# 3_waffling60-MXHS-ANSI_mcu.net
KiCad netlist of a schematic drawn in Altium Designer
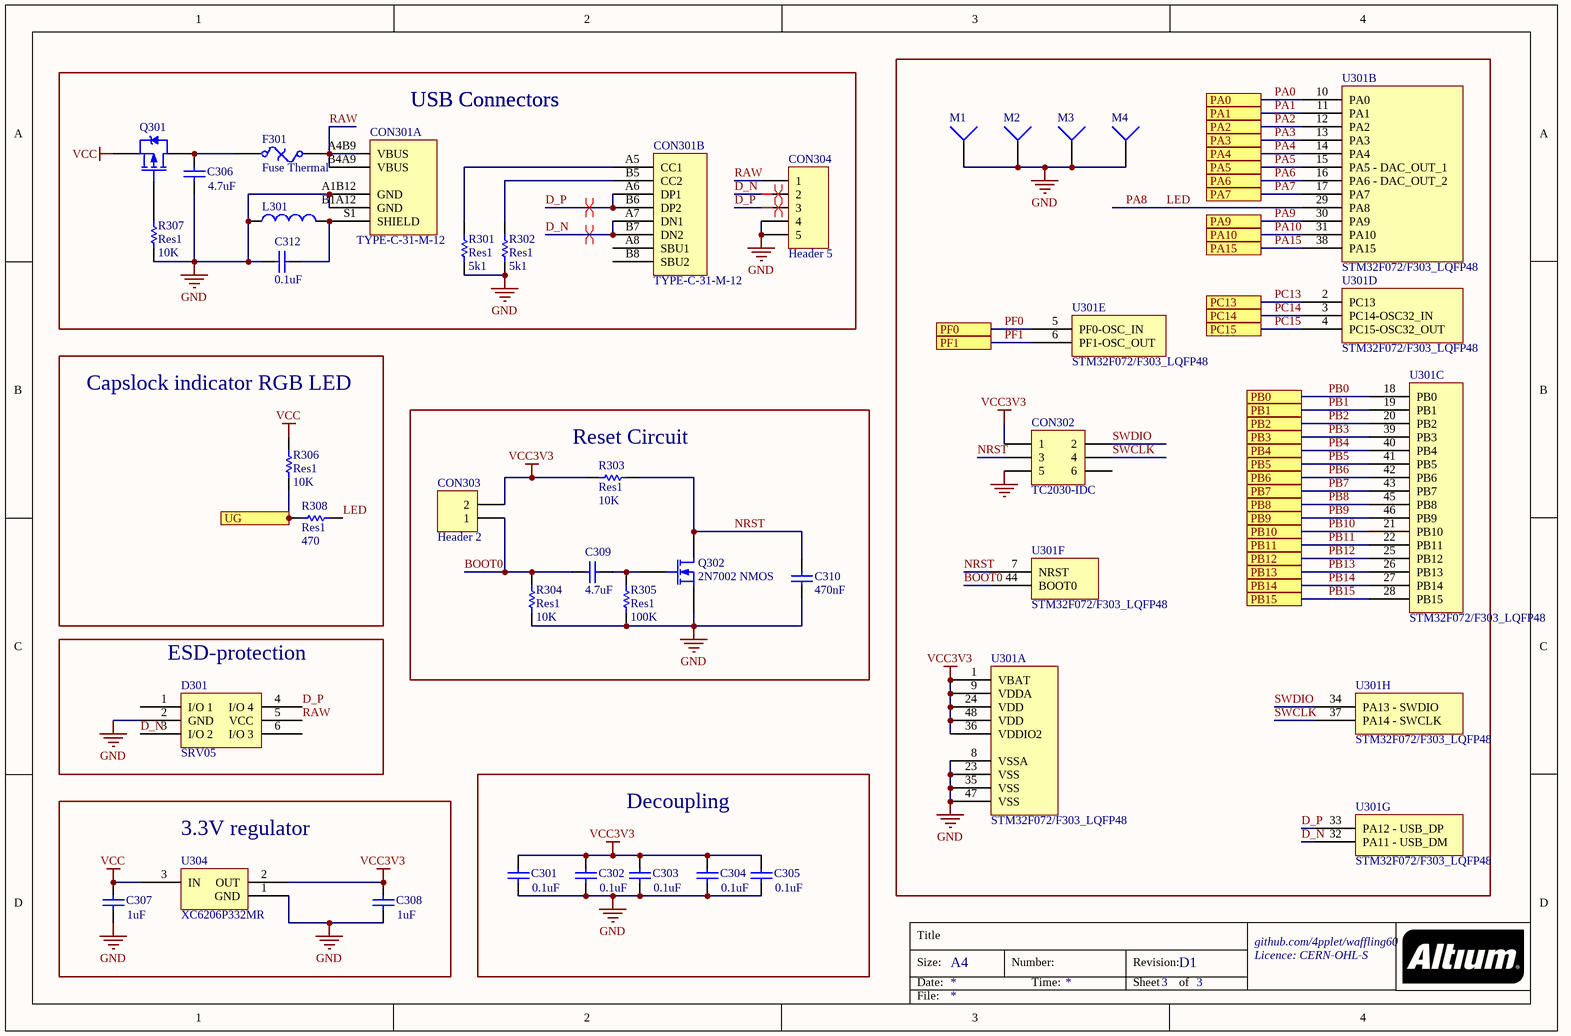
[diagram p0: 3_waffling60-MXHS-ANSI_mcu.SchDoc]

(export (version "E")
  (design (tool "Eeschema 10.0.6"))
  (components
    (comp (ref "C301")
      (value "0.1uF")
      (footprint "C0603[1608]")
      (description "Capacitor")
      (fields (field (name "LCSC PART #") "C14663") (field (name "MRF.PART") "CC0603KRX7R9BB104"))
      (libsource (lib "Miscellaneous Devices") (part "Cap"))
    )
    (comp (ref "C302")
      (value "0.1uF")
      (footprint "C0603[1608]")
      (description "Capacitor")
      (fields (field (name "LCSC PART #") "C14663") (field (name "MRF.PART") "CC0603KRX7R9BB104"))
      (libsource (lib "Miscellaneous Devices") (part "Cap"))
    )
    (comp (ref "C303")
      (value "0.1uF")
      (footprint "C0603[1608]")
      (description "Capacitor")
      (fields (field (name "LCSC PART #") "C14663") (field (name "MRF.PART") "CC0603KRX7R9BB104"))
      (libsource (lib "Miscellaneous Devices") (part "Cap"))
    )
    (comp (ref "C304")
      (value "0.1uF")
      (footprint "C0603[1608]")
      (description "Capacitor")
      (fields (field (name "LCSC PART #") "C14663") (field (name "MRF.PART") "CC0603KRX7R9BB104"))
      (libsource (lib "Miscellaneous Devices") (part "Cap"))
    )
    (comp (ref "C305")
      (value "0.1uF")
      (footprint "C0603[1608]")
      (description "Capacitor")
      (fields (field (name "LCSC PART #") "C14663") (field (name "MRF.PART") "CC0603KRX7R9BB104"))
      (libsource (lib "Miscellaneous Devices") (part "Cap"))
    )
    (comp (ref "C306")
      (value "4.7uF")
      (footprint "C0603[1608]")
      (description "Capacitor")
      (fields (field (name "LCSC PART #") "C19666") (field (name "MRF.PART") "CL10A475KO8NNNC"))
      (libsource (lib "Miscellaneous Devices") (part "Cap"))
    )
    (comp (ref "C307")
      (value "1uF")
      (footprint "C0603[1608]")
      (description "Capacitor")
      (fields (field (name "LCSC PART #") "C15849") (field (name "MRF.PART") "CL10A105KB8NNNC"))
      (libsource (lib "Miscellaneous Devices") (part "Cap"))
    )
    (comp (ref "C308")
      (value "1uF")
      (footprint "C0603[1608]")
      (description "Capacitor")
      (fields (field (name "LCSC PART #") "C15849") (field (name "MRF.PART") "CL10A105KB8NNNC"))
      (libsource (lib "Miscellaneous Devices") (part "Cap"))
    )
    (comp (ref "C309")
      (value "4.7uF")
      (footprint "C0603[1608]")
      (description "Capacitor")
      (fields (field (name "LCSC PART #") "C19666") (field (name "MRF.PART") "CL10A475KO8NNNC"))
      (libsource (lib "Miscellaneous Devices") (part "Cap"))
    )
    (comp (ref "C310")
      (value "470nF")
      (footprint "C0603[1608]")
      (description "Capacitor")
      (fields (field (name "LCSC PART #") "C1623") (field (name "MRF.PART") "CL10B474KA8NNNC"))
      (libsource (lib "Miscellaneous Devices") (part "Cap"))
    )
    (comp (ref "C312")
      (value "0.1uF")
      (footprint "C0603[1608]")
      (description "Capacitor")
      (fields (field (name "LCSC PART #") "C14663") (field (name "MRF.PART") "CC0603KRX7R9BB104"))
      (libsource (lib "Miscellaneous Devices") (part "Cap"))
    )
    (comp (ref "CON301")
      (value "TYPE-C-31-M-12")
      (footprint "TYPE-C-31-M-12")
      (fields (field (name "LCSC PART #") "C165948"))
      (libsource (lib "Schlib1") (part "TYPE-C-31-M-12"))
    )
    (comp (ref "CON302")
      (value "TC2030-IDC")
      (footprint "TC2030-IDC-NL")
      (description "Header, 3-Pin, Dual row")
      (libsource (lib "Miscellaneous Connectors") (part "Header 3X2"))
    )
    (comp (ref "CON303")
      (value "Header 2")
      (footprint "HDR1X2")
      (description "Header, 2-Pin")
      (libsource (lib "Miscellaneous Connectors") (part "Header 2"))
    )
    (comp (ref "CON304")
      (value "Header 5")
      (footprint "Molex 781710004")
      (description "JST for USB daughter board")
      (fields (field (name "LCSC PART #") "C2840019") (field (name "MRF.PART") "M1201RS-04-BK"))
      (libsource (lib "Miscellaneous Connectors") (part "Header 5"))
    )
    (comp (ref "D301")
      (value "SRV05")
      (footprint "SOT-23-6")
      (fields (field (name "LCSC PART #") "C85364") (field (name "MRF.PART") "SRV05-4-P-T7"))
      (libsource (lib "Keebs") (part "SRV05"))
    )
    (comp (ref "F301")
      (value "Fuse Thermal")
      (footprint "C1206[3216]")
      (description "Thermal Fuse")
      (fields (field (name "LCSC PART #") "C135338") (field (name "MRF.PART") "ASMD1206-050"))
      (libsource (lib "Miscellaneous Devices") (part "Fuse Thermal"))
    )
    (comp (ref "L301")
      (value "Inductor")
      (footprint "L0805")
      (fields (field (name "LCSC PART #") "C1015") (field (name "MRF.PART") "GZ2012D101TF"))
      (libsource (lib "Simulation Generic Components") (part "Inductor"))
    )
    (comp (ref "M1")
      (value "Socket")
      (footprint "mounting_hole")
      (libsource (lib "Miscellaneous Connectors") (part "Socket"))
    )
    (comp (ref "M2")
      (value "Socket")
      (footprint "mounting_hole")
      (libsource (lib "Miscellaneous Connectors") (part "Socket"))
    )
    (comp (ref "M3")
      (value "Socket")
      (footprint "mounting_hole")
      (libsource (lib "Miscellaneous Connectors") (part "Socket"))
    )
    (comp (ref "M4")
      (value "Socket")
      (footprint "mounting_hole")
      (libsource (lib "Miscellaneous Connectors") (part "Socket"))
    )
    (comp (ref "Q301")
      (value "PMOS-2")
      (footprint "SOT-23-3")
      (description "P-Channel Power MOSFET")
      (fields (field (name "LCSC PART #") "C10487") (field (name "MRF.PART") "SI2301CDS-T1-GE3"))
      (libsource (lib "Miscellaneous Devices") (part "PMOS-2"))
    )
    (comp (ref "Q302")
      (value "2N7002 NMOS")
      (footprint "SOT-23-3")
      (description "N-Channel MOSFET")
      (fields (field (name "LCSC PART #") "C8545") (field (name "MRF.PART") "2N7002"))
      (libsource (lib "Miscellaneous Devices") (part "MOSFET-N"))
    )
    (comp (ref "R301")
      (value "Res1")
      (footprint "R0603[1608]")
      (description "Resistor")
      (fields
        (field (name "ALTIUM_VALUE") "5k1")
        (field (name "LCSC PART #") "C23186")
        (field (name "MRF.PART") "0603WAF5101T5E")
      )
      (libsource (lib "Miscellaneous Devices") (part "Res1"))
    )
    (comp (ref "R302")
      (value "Res1")
      (footprint "R0603[1608]")
      (description "Resistor")
      (fields
        (field (name "ALTIUM_VALUE") "5k1")
        (field (name "LCSC PART #") "C23186")
        (field (name "MRF.PART") "0603WAF5101T5E")
      )
      (libsource (lib "Miscellaneous Devices") (part "Res1"))
    )
    (comp (ref "R303")
      (value "Res1")
      (footprint "R0603[1608]")
      (description "Resistor")
      (fields
        (field (name "ALTIUM_VALUE") "10K")
        (field (name "LCSC PART #") "C25804")
        (field (name "MRF.PART") "0603WAF1002T5E")
      )
      (libsource (lib "Miscellaneous Devices") (part "Res1"))
    )
    (comp (ref "R304")
      (value "Res1")
      (footprint "R0603[1608]")
      (description "Resistor")
      (fields
        (field (name "ALTIUM_VALUE") "10K")
        (field (name "LCSC PART #") "C25804")
        (field (name "MRF.PART") "0603WAF1002T5E")
      )
      (libsource (lib "Miscellaneous Devices") (part "Res1"))
    )
    (comp (ref "R305")
      (value "Res1")
      (footprint "R0603[1608]")
      (description "Resistor")
      (fields
        (field (name "ALTIUM_VALUE") "100K")
        (field (name "LCSC PART #") "C25803")
        (field (name "MRF.PART") "0603WAF1003T5E")
      )
      (libsource (lib "Miscellaneous Devices") (part "Res1"))
    )
    (comp (ref "R306")
      (value "Res1")
      (footprint "R0603[1608]")
      (description "Resistor")
      (fields
        (field (name "ALTIUM_VALUE") "10K")
        (field (name "LCSC PART #") "C25804")
        (field (name "MRF.PART") "0603WAF1002T5E")
      )
      (libsource (lib "Miscellaneous Devices") (part "Res1"))
    )
    (comp (ref "R307")
      (value "Res1")
      (footprint "R0603[1608]")
      (description "Resistor")
      (fields
        (field (name "ALTIUM_VALUE") "10K")
        (field (name "LCSC PART #") "C25804")
        (field (name "MRF.PART") "0603WAF1002T5E")
      )
      (libsource (lib "Miscellaneous Devices") (part "Res1"))
    )
    (comp (ref "R308")
      (value "Res1")
      (footprint "R0603[1608]")
      (description "Resistor")
      (fields
        (field (name "ALTIUM_VALUE") "470")
        (field (name "LCSC PART #") "C23179")
        (field (name "MRF.PART") "0603WAF4700T5E")
      )
      (libsource (lib "Miscellaneous Devices") (part "Res1"))
    )
    (comp (ref "U301")
      (value "STM32F072/F303_LQFP48")
      (footprint "STM32 - COMBO 7X7MM")
      (fields (field (name "LCSC PART #") "C915660") (field (name "MRF.PART") "APM32F072CBT6"))
      (libsource (lib "") (part "STM32F072/F303_LQFP48_1"))
    )
    (comp (ref "U304")
      (value "XC6206P332MR")
      (footprint "SOT-23-3")
      (fields (field (name "LCSC PART #") "C5446"))
      (libsource (lib "Keebs") (part "SOT23 LDO"))
    )
  )
  (nets
    (net (code "1") (name "/BOOT0") (class "Default")
      (node (ref "C309") (pin "1") (pinfunction "1_1") (pintype "passive"))
      (node (ref "CON303") (pin "1") (pinfunction "1_1") (pintype "passive"))
      (node (ref "R304") (pin "1") (pinfunction "1_1") (pintype "passive"))
      (node (ref "U301") (pin "44") (pinfunction "BOOT0_44") (pintype "passive"))
    )
    (net (code "2") (name "/D_N") (class "Default")
      (node (ref "CON301") (pin "A7") (pinfunction "DN1_A7") (pintype "passive"))
      (node (ref "CON301") (pin "B7") (pinfunction "DN2_B7") (pintype "passive"))
      (node (ref "CON304") (pin "2") (pinfunction "2_2") (pintype "passive"))
      (node (ref "D301") (pin "3") (pinfunction "I/O_2_3") (pintype "passive"))
      (node (ref "U301") (pin "32") (pinfunction "PA11_-_USB_DM_32") (pintype "passive"))
    )
    (net (code "3") (name "/D_P") (class "Default")
      (node (ref "CON301") (pin "A6") (pinfunction "DP1_A6") (pintype "passive"))
      (node (ref "CON301") (pin "B6") (pinfunction "DP2_B6") (pintype "passive"))
      (node (ref "CON304") (pin "3") (pinfunction "3_3") (pintype "passive"))
      (node (ref "D301") (pin "4") (pinfunction "I/O_4_4") (pintype "passive"))
      (node (ref "U301") (pin "33") (pinfunction "PA12_-_USB_DP_33") (pintype "passive"))
    )
    (net (code "4") (name "/LED") (class "Default")
      (node (ref "R308") (pin "2") (pinfunction "2_2") (pintype "passive"))
      (node (ref "U301") (pin "29") (pinfunction "PA8_29") (pintype "passive"))
    )
    (net (code "5") (name "/NRST") (class "Default")
      (node (ref "C310") (pin "1") (pinfunction "1_1") (pintype "passive"))
      (node (ref "CON302") (pin "3") (pinfunction "3_3") (pintype "passive"))
      (node (ref "Q302") (pin "3") (pinfunction "D_3") (pintype "passive"))
      (node (ref "R303") (pin "2") (pinfunction "2_2") (pintype "passive"))
      (node (ref "U301") (pin "7") (pinfunction "NRST_7") (pintype "passive"))
    )
    (net (code "6") (name "/PA0") (class "Default")
      (node (ref "U301") (pin "10") (pinfunction "PA0_10") (pintype "passive"))
    )
    (net (code "7") (name "/PA1") (class "Default")
      (node (ref "U301") (pin "11") (pinfunction "PA1_11") (pintype "passive"))
    )
    (net (code "8") (name "/PA2") (class "Default")
      (node (ref "U301") (pin "12") (pinfunction "PA2_12") (pintype "passive"))
    )
    (net (code "9") (name "/PA3") (class "Default")
      (node (ref "U301") (pin "13") (pinfunction "PA3_13") (pintype "passive"))
    )
    (net (code "10") (name "/PA4") (class "Default")
      (node (ref "U301") (pin "14") (pinfunction "PA4_14") (pintype "passive"))
    )
    (net (code "11") (name "/PA5") (class "Default")
      (node (ref "U301") (pin "15") (pinfunction "PA5_-_DAC_OUT_1_15") (pintype "passive"))
    )
    (net (code "12") (name "/PA6") (class "Default")
      (node (ref "U301") (pin "16") (pinfunction "PA6_-_DAC_OUT_2_16") (pintype "passive"))
    )
    (net (code "13") (name "/PA7") (class "Default")
      (node (ref "U301") (pin "17") (pinfunction "PA7_17") (pintype "passive"))
    )
    (net (code "14") (name "/PA9") (class "Default")
      (node (ref "U301") (pin "30") (pinfunction "PA9_30") (pintype "passive"))
    )
    (net (code "15") (name "/PA10") (class "Default")
      (node (ref "U301") (pin "31") (pinfunction "PA10_31") (pintype "passive"))
    )
    (net (code "16") (name "/PA15") (class "Default")
      (node (ref "U301") (pin "38") (pinfunction "PA15_38") (pintype "passive"))
    )
    (net (code "17") (name "/PB0") (class "Default")
      (node (ref "U301") (pin "18") (pinfunction "PB0_18") (pintype "passive"))
    )
    (net (code "18") (name "/PB1") (class "Default")
      (node (ref "U301") (pin "19") (pinfunction "PB1_19") (pintype "passive"))
    )
    (net (code "19") (name "/PB2") (class "Default")
      (node (ref "U301") (pin "20") (pinfunction "PB2_20") (pintype "passive"))
    )
    (net (code "20") (name "/PB3") (class "Default")
      (node (ref "U301") (pin "39") (pinfunction "PB3_39") (pintype "passive"))
    )
    (net (code "21") (name "/PB4") (class "Default")
      (node (ref "U301") (pin "40") (pinfunction "PB4_40") (pintype "passive"))
    )
    (net (code "22") (name "/PB5") (class "Default")
      (node (ref "U301") (pin "41") (pinfunction "PB5_41") (pintype "passive"))
    )
    (net (code "23") (name "/PB6") (class "Default")
      (node (ref "U301") (pin "42") (pinfunction "PB6_42") (pintype "passive"))
    )
    (net (code "24") (name "/PB7") (class "Default")
      (node (ref "U301") (pin "43") (pinfunction "PB7_43") (pintype "passive"))
    )
    (net (code "25") (name "/PB8") (class "Default")
      (node (ref "U301") (pin "45") (pinfunction "PB8_45") (pintype "passive"))
    )
    (net (code "26") (name "/PB9") (class "Default")
      (node (ref "U301") (pin "46") (pinfunction "PB9_46") (pintype "passive"))
    )
    (net (code "27") (name "/PB10") (class "Default")
      (node (ref "U301") (pin "21") (pinfunction "PB10_21") (pintype "passive"))
    )
    (net (code "28") (name "/PB11") (class "Default")
      (node (ref "U301") (pin "22") (pinfunction "PB11_22") (pintype "passive"))
    )
    (net (code "29") (name "/PB12") (class "Default")
      (node (ref "U301") (pin "25") (pinfunction "PB12_25") (pintype "passive"))
    )
    (net (code "30") (name "/PB13") (class "Default")
      (node (ref "U301") (pin "26") (pinfunction "PB13_26") (pintype "passive"))
    )
    (net (code "31") (name "/PB14") (class "Default")
      (node (ref "U301") (pin "27") (pinfunction "PB14_27") (pintype "passive"))
    )
    (net (code "32") (name "/PB15") (class "Default")
      (node (ref "U301") (pin "28") (pinfunction "PB15_28") (pintype "passive"))
    )
    (net (code "33") (name "/PC13") (class "Default")
      (node (ref "U301") (pin "2") (pinfunction "PC13_2") (pintype "passive"))
    )
    (net (code "34") (name "/PC14") (class "Default")
      (node (ref "U301") (pin "3") (pinfunction "PC14-OSC32_IN_3") (pintype "passive"))
    )
    (net (code "35") (name "/PC15") (class "Default")
      (node (ref "U301") (pin "4") (pinfunction "PC15-OSC32_OUT_4") (pintype "passive"))
    )
    (net (code "36") (name "/PF0") (class "Default")
      (node (ref "U301") (pin "5") (pinfunction "PF0-OSC_IN_5") (pintype "passive"))
    )
    (net (code "37") (name "/PF1") (class "Default")
      (node (ref "U301") (pin "6") (pinfunction "PF1-OSC_OUT_6") (pintype "passive"))
    )
    (net (code "38") (name "/RAW") (class "Default")
      (node (ref "CON301") (pin "A4B9") (pinfunction "VBUS_A4B9") (pintype "passive"))
      (node (ref "CON301") (pin "B4A9") (pinfunction "VBUS_B4A9") (pintype "passive"))
      (node (ref "CON304") (pin "1") (pinfunction "1_1") (pintype "passive"))
      (node (ref "D301") (pin "5") (pinfunction "VCC_5") (pintype "passive"))
      (node (ref "F301") (pin "2") (pinfunction "2_2") (pintype "passive"))
    )
    (net (code "39") (name "/SWCLK") (class "Default")
      (node (ref "CON302") (pin "4") (pinfunction "4_4") (pintype "passive"))
      (node (ref "U301") (pin "37") (pinfunction "PA14_-_SWCLK_37") (pintype "passive"))
    )
    (net (code "40") (name "/SWDIO") (class "Default")
      (node (ref "CON302") (pin "2") (pinfunction "2_2") (pintype "passive"))
      (node (ref "U301") (pin "34") (pinfunction "PA13_-_SWDIO_34") (pintype "passive"))
    )
    (net (code "41") (name "/UG") (class "Default")
      (node (ref "R306") (pin "2") (pinfunction "2_2") (pintype "passive"))
      (node (ref "R308") (pin "1") (pinfunction "1_1") (pintype "passive"))
    )
    (net (code "42") (name "GND") (class "Default")
      (node (ref "C301") (pin "1") (pinfunction "1_1") (pintype "passive"))
      (node (ref "C302") (pin "1") (pinfunction "1_1") (pintype "passive"))
      (node (ref "C303") (pin "1") (pinfunction "1_1") (pintype "passive"))
      (node (ref "C304") (pin "1") (pinfunction "1_1") (pintype "passive"))
      (node (ref "C305") (pin "1") (pinfunction "1_1") (pintype "passive"))
      (node (ref "C306") (pin "1") (pinfunction "1_1") (pintype "passive"))
      (node (ref "C307") (pin "1") (pinfunction "1_1") (pintype "passive"))
      (node (ref "C308") (pin "1") (pinfunction "1_1") (pintype "passive"))
      (node (ref "C310") (pin "2") (pinfunction "2_2") (pintype "passive"))
      (node (ref "C312") (pin "1") (pinfunction "1_1") (pintype "passive"))
      (node (ref "CON301") (pin "A1B12") (pinfunction "GND_A1B12") (pintype "passive"))
      (node (ref "CON301") (pin "B1A12") (pinfunction "GND_B1A12") (pintype "passive"))
      (node (ref "CON302") (pin "5") (pinfunction "5_5") (pintype "passive"))
      (node (ref "CON304") (pin "4") (pinfunction "4_4") (pintype "passive"))
      (node (ref "CON304") (pin "5") (pinfunction "5_5") (pintype "passive"))
      (node (ref "D301") (pin "2") (pinfunction "GND_2") (pintype "passive"))
      (node (ref "L301") (pin "1") (pinfunction "1_1") (pintype "passive"))
      (node (ref "M1") (pin "1") (pinfunction "1_1") (pintype "passive"))
      (node (ref "M2") (pin "1") (pinfunction "1_1") (pintype "passive"))
      (node (ref "M3") (pin "1") (pinfunction "1_1") (pintype "passive"))
      (node (ref "M4") (pin "1") (pinfunction "1_1") (pintype "passive"))
      (node (ref "Q302") (pin "2") (pinfunction "S_2") (pintype "passive"))
      (node (ref "R301") (pin "2") (pinfunction "2_2") (pintype "passive"))
      (node (ref "R302") (pin "2") (pinfunction "2_2") (pintype "passive"))
      (node (ref "R304") (pin "2") (pinfunction "2_2") (pintype "passive"))
      (node (ref "R305") (pin "2") (pinfunction "2_2") (pintype "passive"))
      (node (ref "R307") (pin "2") (pinfunction "2_2") (pintype "passive"))
      (node (ref "U301") (pin "23") (pinfunction "VSS_23") (pintype "passive"))
      (node (ref "U301") (pin "35") (pinfunction "VSS_35") (pintype "passive"))
      (node (ref "U301") (pin "47") (pinfunction "VSS_47") (pintype "passive"))
      (node (ref "U301") (pin "8") (pinfunction "VSSA_8") (pintype "passive"))
      (node (ref "U304") (pin "1") (pinfunction "GND_1") (pintype "passive"))
    )
    (net (code "43") (name "Net-(CON301A-SHIELD)") (class "Default")
      (node (ref "C312") (pin "2") (pinfunction "2_2") (pintype "passive"))
      (node (ref "CON301") (pin "S1") (pinfunction "SHIELD_S1") (pintype "passive"))
      (node (ref "L301") (pin "2") (pinfunction "2_2") (pintype "passive"))
    )
    (net (code "44") (name "Net-(CON301B-CC1)") (class "Default")
      (node (ref "CON301") (pin "A5") (pinfunction "CC1_A5") (pintype "passive"))
      (node (ref "R301") (pin "1") (pinfunction "1_1") (pintype "passive"))
    )
    (net (code "45") (name "Net-(CON301B-CC2)") (class "Default")
      (node (ref "CON301") (pin "B5") (pinfunction "CC2_B5") (pintype "passive"))
      (node (ref "R302") (pin "1") (pinfunction "1_1") (pintype "passive"))
    )
    (net (code "46") (name "Net-(Q301-D)") (class "Default")
      (node (ref "C306") (pin "2") (pinfunction "2_2") (pintype "passive"))
      (node (ref "F301") (pin "1") (pinfunction "1_1") (pintype "passive"))
      (node (ref "Q301") (pin "3") (pinfunction "D_3") (pintype "passive"))
    )
    (net (code "47") (name "Net-(Q301-G)") (class "Default")
      (node (ref "Q301") (pin "1") (pinfunction "G_1") (pintype "passive"))
      (node (ref "R307") (pin "1") (pinfunction "1_1") (pintype "passive"))
    )
    (net (code "48") (name "Net-(Q302-G)") (class "Default")
      (node (ref "C309") (pin "2") (pinfunction "2_2") (pintype "passive"))
      (node (ref "Q302") (pin "1") (pinfunction "G_1") (pintype "passive"))
      (node (ref "R305") (pin "1") (pinfunction "1_1") (pintype "passive"))
    )
    (net (code "49") (name "VCC") (class "Default")
      (node (ref "C307") (pin "2") (pinfunction "2_2") (pintype "passive"))
      (node (ref "Q301") (pin "2") (pinfunction "S_2") (pintype "passive"))
      (node (ref "R306") (pin "1") (pinfunction "1_1") (pintype "passive"))
      (node (ref "U304") (pin "3") (pinfunction "IN_3") (pintype "passive"))
    )
    (net (code "50") (name "VCC3V3") (class "Default")
      (node (ref "C301") (pin "2") (pinfunction "2_2") (pintype "passive"))
      (node (ref "C302") (pin "2") (pinfunction "2_2") (pintype "passive"))
      (node (ref "C303") (pin "2") (pinfunction "2_2") (pintype "passive"))
      (node (ref "C304") (pin "2") (pinfunction "2_2") (pintype "passive"))
      (node (ref "C305") (pin "2") (pinfunction "2_2") (pintype "passive"))
      (node (ref "C308") (pin "2") (pinfunction "2_2") (pintype "passive"))
      (node (ref "CON302") (pin "1") (pinfunction "1_1") (pintype "passive"))
      (node (ref "CON303") (pin "2") (pinfunction "2_2") (pintype "passive"))
      (node (ref "R303") (pin "1") (pinfunction "1_1") (pintype "passive"))
      (node (ref "U301") (pin "1") (pinfunction "VBAT_1") (pintype "passive"))
      (node (ref "U301") (pin "24") (pinfunction "VDD_24") (pintype "passive"))
      (node (ref "U301") (pin "36") (pinfunction "VDDIO2_36") (pintype "passive"))
      (node (ref "U301") (pin "48") (pinfunction "VDD_48") (pintype "passive"))
      (node (ref "U301") (pin "9") (pinfunction "VDDA_9") (pintype "passive"))
      (node (ref "U304") (pin "2") (pinfunction "OUT_2") (pintype "passive"))
    )
    (net (code "51") (name "unconnected-(CON301B-SBU1-PadA8)") (class "Default")
      (node (ref "CON301") (pin "A8") (pinfunction "SBU1_A8") (pintype "passive"))
    )
    (net (code "52") (name "unconnected-(CON301B-SBU2-PadB8)") (class "Default")
      (node (ref "CON301") (pin "B8") (pinfunction "SBU2_B8") (pintype "passive"))
    )
    (net (code "53") (name "unconnected-(CON302-Pad6)") (class "Default")
      (node (ref "CON302") (pin "6") (pinfunction "6_6") (pintype "passive"))
    )
    (net (code "54") (name "unconnected-(D301-I{slash}O_1-Pad1)") (class "Default")
      (node (ref "D301") (pin "1") (pinfunction "I/O_1_1") (pintype "passive"))
    )
    (net (code "55") (name "unconnected-(D301-I{slash}O_3-Pad6)") (class "Default")
      (node (ref "D301") (pin "6") (pinfunction "I/O_3_6") (pintype "passive"))
    )
  )
)
